# EiBotBoard-v24.net
KiCad netlist of a schematic drawn in EAGLE
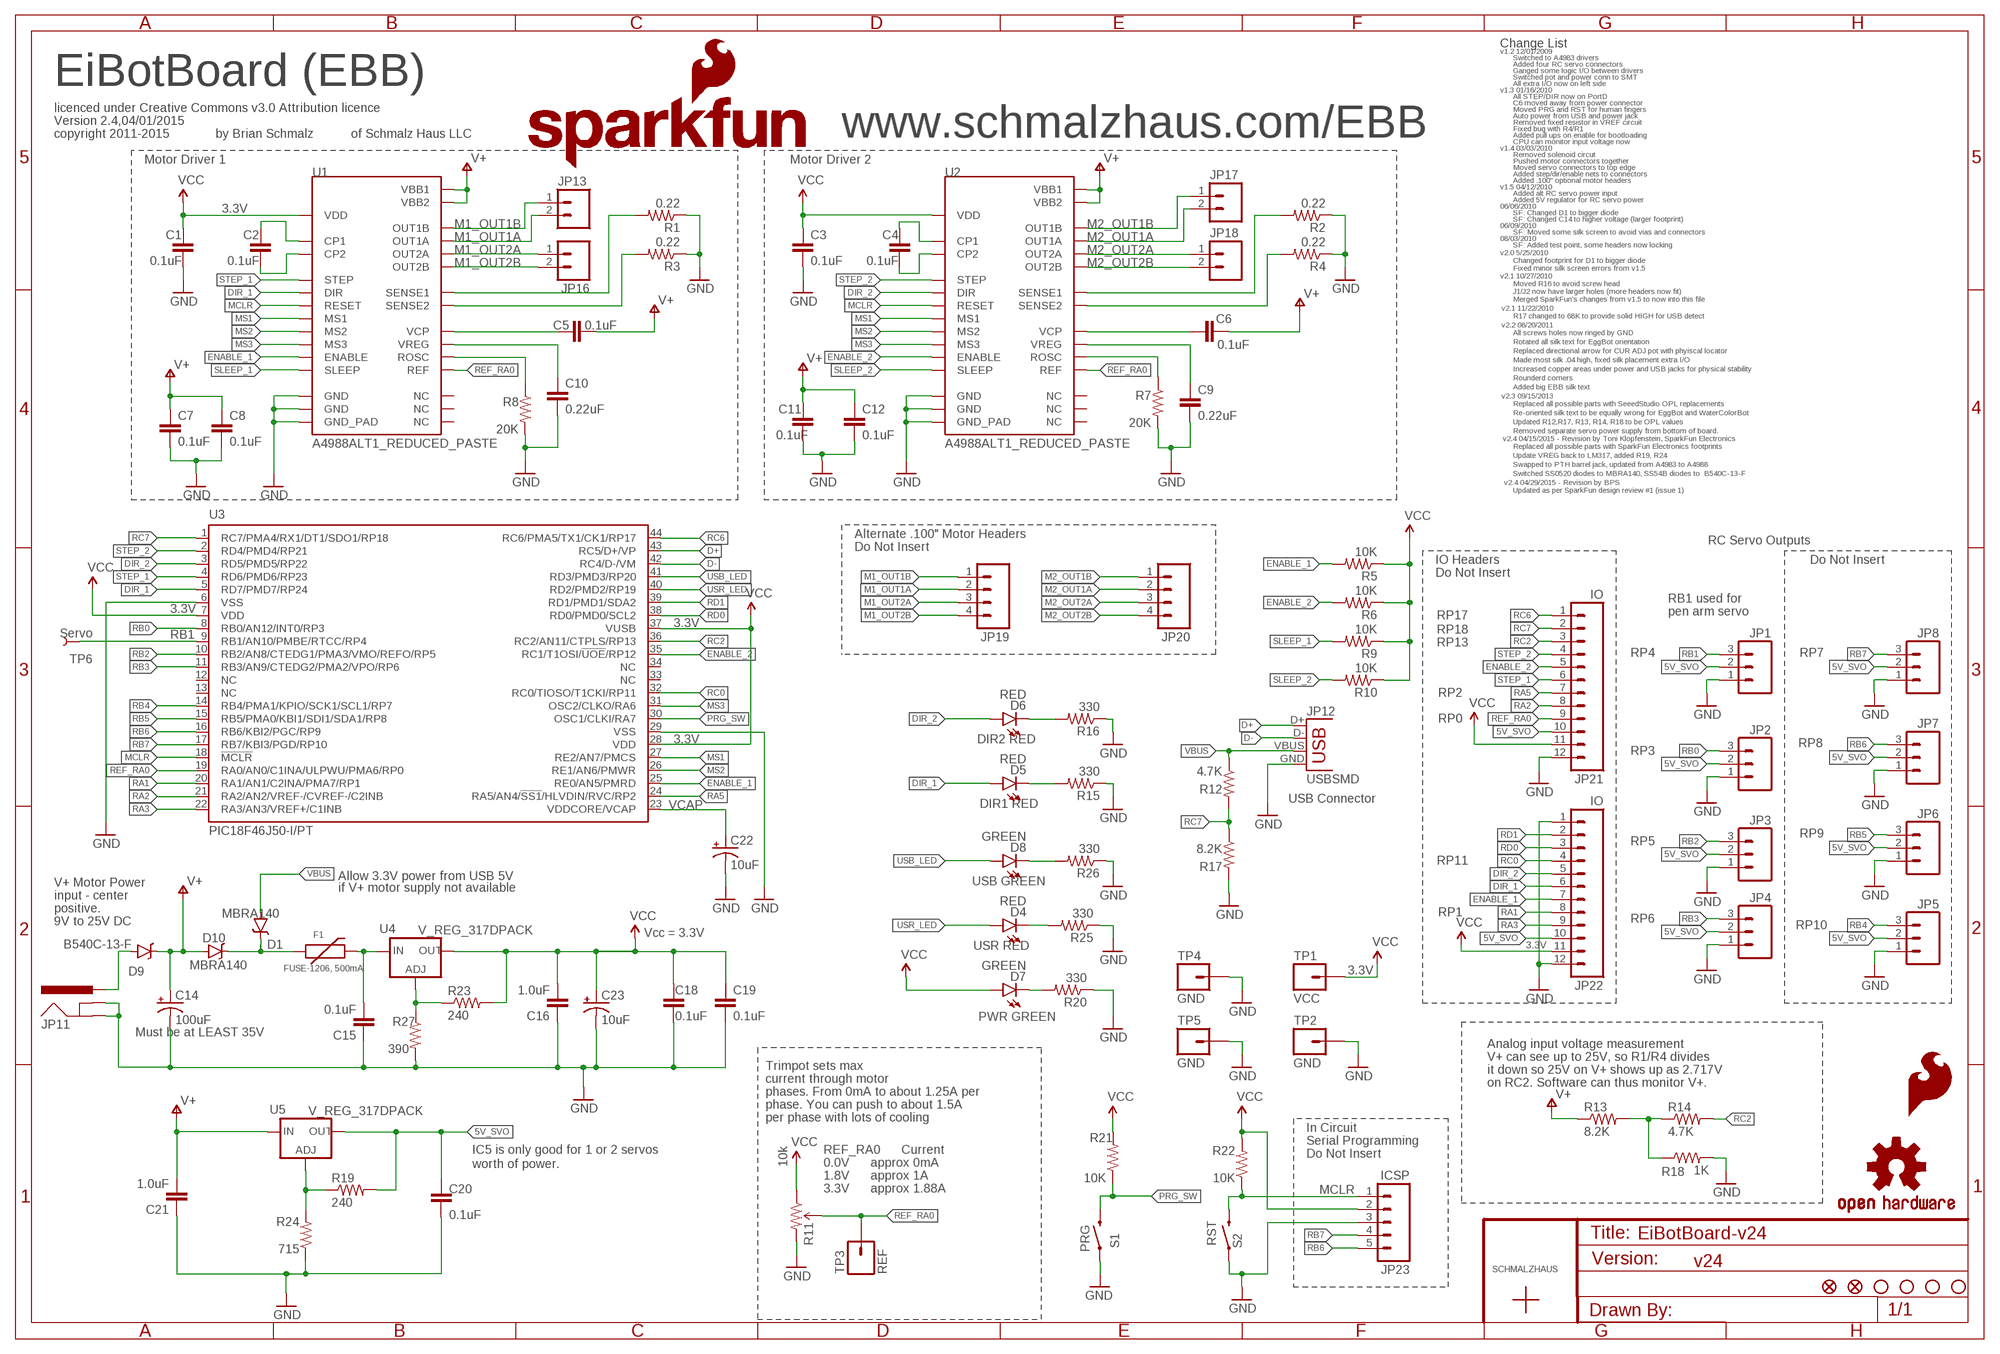
[diagram p0: schematic, sheet 1]

(export (version "E")
  (design (tool "Eeschema 10.0.6"))
  (components
    (comp (ref "C1")
      (value "0.1uF")
      (footprint "eagle-import:0603-CAP")
      (libsource (lib "eagle-import") (part "0.1UF-100V-10%(0603)"))
    )
    (comp (ref "C2")
      (value "0.1uF")
      (footprint "eagle-import:0603-CAP")
      (libsource (lib "eagle-import") (part "0.1UF-100V-10%(0603)"))
    )
    (comp (ref "C3")
      (value "0.1uF")
      (footprint "eagle-import:0603-CAP")
      (libsource (lib "eagle-import") (part "0.1UF-100V-10%(0603)"))
    )
    (comp (ref "C4")
      (value "0.1uF")
      (footprint "eagle-import:0603-CAP")
      (libsource (lib "eagle-import") (part "0.1UF-100V-10%(0603)"))
    )
    (comp (ref "C5")
      (value "0.1uF")
      (footprint "eagle-import:0603-CAP")
      (libsource (lib "eagle-import") (part "0.1UF-100V-10%(0603)"))
    )
    (comp (ref "C6")
      (value "0.1uF")
      (footprint "eagle-import:0603-CAP")
      (libsource (lib "eagle-import") (part "0.1UF-100V-10%(0603)"))
    )
    (comp (ref "C7")
      (value "0.1uF")
      (footprint "eagle-import:0603-CAP")
      (libsource (lib "eagle-import") (part "0.1UF-100V-10%(0603)"))
    )
    (comp (ref "C8")
      (value "0.1uF")
      (footprint "eagle-import:0603-CAP")
      (libsource (lib "eagle-import") (part "0.1UF-100V-10%(0603)"))
    )
    (comp (ref "C9")
      (value "0.22uF")
      (footprint "eagle-import:0603-CAP")
      (libsource (lib "eagle-import") (part "0.22UF50V-20%,+80%(0603)"))
    )
    (comp (ref "C10")
      (value "0.22uF")
      (footprint "eagle-import:0603-CAP")
      (libsource (lib "eagle-import") (part "0.22UF50V-20%,+80%(0603)"))
    )
    (comp (ref "C11")
      (value "0.1uF")
      (footprint "eagle-import:0603-CAP")
      (libsource (lib "eagle-import") (part "0.1UF-100V-10%(0603)"))
    )
    (comp (ref "C12")
      (value "0.1uF")
      (footprint "eagle-import:0603-CAP")
      (libsource (lib "eagle-import") (part "0.1UF-100V-10%(0603)"))
    )
    (comp (ref "C14")
      (value "100uF")
      (footprint "eagle-import:NIC_10X10.5_CAP")
      (libsource (lib "eagle-import") (part "100UF-63V-20%(ELECT)"))
    )
    (comp (ref "C15")
      (value "0.1uF")
      (footprint "eagle-import:0603-CAP")
      (libsource (lib "eagle-import") (part "0.1UF-100V-10%(0603)"))
    )
    (comp (ref "C16")
      (value "1.0uF")
      (footprint "eagle-import:0603-CAP")
      (libsource (lib "eagle-import") (part "1.0UF-16V-10%(0603)"))
    )
    (comp (ref "C18")
      (value "0.1uF")
      (footprint "eagle-import:0603-CAP")
      (libsource (lib "eagle-import") (part "0.1UF-100V-10%(0603)"))
    )
    (comp (ref "C19")
      (value "0.1uF")
      (footprint "eagle-import:0603-CAP")
      (libsource (lib "eagle-import") (part "0.1UF-100V-10%(0603)"))
    )
    (comp (ref "C20")
      (value "0.1uF")
      (footprint "eagle-import:0603-CAP")
      (libsource (lib "eagle-import") (part "0.1UF-100V-10%(0603)"))
    )
    (comp (ref "C21")
      (value "1.0uF")
      (footprint "eagle-import:0603-CAP")
      (libsource (lib "eagle-import") (part "1.0UF-16V-10%(0603)"))
    )
    (comp (ref "C22")
      (value "10uF")
      (footprint "eagle-import:EIA3528")
      (libsource (lib "eagle-import") (part "10UF-20V-10%(TANT)"))
    )
    (comp (ref "C23")
      (value "10uF")
      (footprint "eagle-import:EIA3528")
      (libsource (lib "eagle-import") (part "10UF-20V-10%(TANT)"))
    )
    (comp (ref "D1")
      (value "MBRA140")
      (footprint "eagle-import:SMA-DIODE")
      (libsource (lib "eagle-import") (part "DIODE-SCHOTTKY-MBRA140"))
    )
    (comp (ref "D4")
      (value "RED")
      (footprint "eagle-import:LED-0603")
      (libsource (lib "eagle-import") (part "LED-RED0603"))
    )
    (comp (ref "D5")
      (value "RED")
      (footprint "eagle-import:LED-0603")
      (libsource (lib "eagle-import") (part "LED-RED0603"))
    )
    (comp (ref "D6")
      (value "RED")
      (footprint "eagle-import:LED-0603")
      (libsource (lib "eagle-import") (part "LED-RED0603"))
    )
    (comp (ref "D7")
      (value "GREEN")
      (footprint "eagle-import:LED-0603")
      (libsource (lib "eagle-import") (part "LED-GREEN0603"))
    )
    (comp (ref "D8")
      (value "GREEN")
      (footprint "eagle-import:LED-0603")
      (libsource (lib "eagle-import") (part "LED-GREEN0603"))
    )
    (comp (ref "D9")
      (value "B540C-13-F")
      (footprint "eagle-import:SMC")
      (libsource (lib "eagle-import") (part "DIODE-SCHOTTKY-B540C-13-F"))
    )
    (comp (ref "D10")
      (value "MBRA140")
      (footprint "eagle-import:SMA-DIODE")
      (libsource (lib "eagle-import") (part "DIODE-SCHOTTKY-MBRA140"))
    )
    (comp (ref "F1")
      (value "FUSE-1206, 500mA")
      (footprint "eagle-import:PTC-1206")
      (libsource (lib "eagle-import") (part "PTCTHERMISTOR1206"))
    )
    (comp (ref "JP1")
      (value "M03LOCK_NO_SILK")
      (footprint "eagle-import:1X03_LOCK_NO_SILK")
      (libsource (lib "eagle-import") (part "M03LOCK_NO_SILK"))
    )
    (comp (ref "JP2")
      (value "M03LOCK_NO_SILK")
      (footprint "eagle-import:1X03_LOCK_NO_SILK")
      (libsource (lib "eagle-import") (part "M03LOCK_NO_SILK"))
    )
    (comp (ref "JP3")
      (value "M03LOCK_NO_SILK")
      (footprint "eagle-import:1X03_LOCK_NO_SILK")
      (libsource (lib "eagle-import") (part "M03LOCK_NO_SILK"))
    )
    (comp (ref "JP4")
      (value "M03LOCK_NO_SILK")
      (footprint "eagle-import:1X03_LOCK_NO_SILK")
      (libsource (lib "eagle-import") (part "M03LOCK_NO_SILK"))
    )
    (comp (ref "JP5")
      (value "M03LOCK_NO_SILK")
      (footprint "eagle-import:1X03_LOCK_NO_SILK")
      (libsource (lib "eagle-import") (part "M03LOCK_NO_SILK"))
    )
    (comp (ref "JP6")
      (value "M03LOCK_NO_SILK")
      (footprint "eagle-import:1X03_LOCK_NO_SILK")
      (libsource (lib "eagle-import") (part "M03LOCK_NO_SILK"))
    )
    (comp (ref "JP7")
      (value "M03LOCK_NO_SILK")
      (footprint "eagle-import:1X03_LOCK_NO_SILK")
      (libsource (lib "eagle-import") (part "M03LOCK_NO_SILK"))
    )
    (comp (ref "JP8")
      (value "M03LOCK_NO_SILK")
      (footprint "eagle-import:1X03_LOCK_NO_SILK")
      (libsource (lib "eagle-import") (part "M03LOCK_NO_SILK"))
    )
    (comp (ref "JP11")
      (value "POWER_JACKPTH_LOCK")
      (footprint "eagle-import:POWER_JACK_PTH_LOCK")
      (libsource (lib "eagle-import") (part "POWER_JACKPTH_LOCK"))
    )
    (comp (ref "JP12")
      (value "USBSMD")
      (footprint "eagle-import:USB-MINIB")
      (libsource (lib "eagle-import") (part "USBSMD"))
    )
    (comp (ref "JP13")
      (value "M023.5MM_LOCK")
      (footprint "eagle-import:SCREWTERMINAL-3.5MM-2_LOCK")
      (libsource (lib "eagle-import") (part "M023.5MM_LOCK"))
    )
    (comp (ref "JP14")
      (value "FIDUCIAL1X2")
      (footprint "eagle-import:FIDUCIAL-1X2")
      (libsource (lib "eagle-import") (part "FIDUCIAL1X2"))
    )
    (comp (ref "JP15")
      (value "FIDUCIAL1X2")
      (footprint "eagle-import:FIDUCIAL-1X2")
      (libsource (lib "eagle-import") (part "FIDUCIAL1X2"))
    )
    (comp (ref "JP16")
      (value "M023.5MM_LOCK")
      (footprint "eagle-import:SCREWTERMINAL-3.5MM-2_LOCK")
      (libsource (lib "eagle-import") (part "M023.5MM_LOCK"))
    )
    (comp (ref "JP17")
      (value "M023.5MM_LOCK")
      (footprint "eagle-import:SCREWTERMINAL-3.5MM-2_LOCK")
      (libsource (lib "eagle-import") (part "M023.5MM_LOCK"))
    )
    (comp (ref "JP18")
      (value "M023.5MM_LOCK")
      (footprint "eagle-import:SCREWTERMINAL-3.5MM-2_LOCK")
      (libsource (lib "eagle-import") (part "M023.5MM_LOCK"))
    )
    (comp (ref "JP19")
      (value "M04POLAR")
      (footprint "eagle-import:MOLEX-1X4")
      (libsource (lib "eagle-import") (part "M04POLAR"))
    )
    (comp (ref "JP20")
      (value "M04POLAR")
      (footprint "eagle-import:MOLEX-1X4")
      (libsource (lib "eagle-import") (part "M04POLAR"))
    )
    (comp (ref "JP21")
      (value "IO")
      (footprint "eagle-import:1X12")
      (libsource (lib "eagle-import") (part "M12PTH"))
    )
    (comp (ref "JP22")
      (value "IO")
      (footprint "eagle-import:1X12")
      (libsource (lib "eagle-import") (part "M12PTH"))
    )
    (comp (ref "JP23")
      (value "ICSP")
      (footprint "eagle-import:1X05_NO_SILK")
      (libsource (lib "eagle-import") (part "M05NO_SILK"))
    )
    (comp (ref "LOGO1")
      (value "OSHW-LOGOS")
      (footprint "eagle-import:OSHW-LOGO-S")
      (libsource (lib "eagle-import") (part "OSHW-LOGOS"))
    )
    (comp (ref "LOGO2")
      (value "SFE_LOGO_FLAME.2_INCH")
      (footprint "eagle-import:SFE_LOGO_FLAME_.2")
      (libsource (lib "eagle-import") (part "SFE_LOGO_FLAME.2_INCH"))
    )
    (comp (ref "LOGO3")
      (value "SFE_LOGO_NAME_FLAME.2_INCH")
      (footprint "eagle-import:SFE_LOGO_NAME_FLAME_.2")
      (libsource (lib "eagle-import") (part "SFE_LOGO_NAME_FLAME.2_INCH"))
    )
    (comp (ref "R1")
      (value "0.22")
      (footprint "eagle-import:0805")
      (libsource (lib "eagle-import") (part "0.22OHM-1/4W-1%(0805)"))
    )
    (comp (ref "R2")
      (value "0.22")
      (footprint "eagle-import:0805")
      (libsource (lib "eagle-import") (part "0.22OHM-1/4W-1%(0805)"))
    )
    (comp (ref "R3")
      (value "0.22")
      (footprint "eagle-import:0805")
      (libsource (lib "eagle-import") (part "0.22OHM-1/4W-1%(0805)"))
    )
    (comp (ref "R4")
      (value "0.22")
      (footprint "eagle-import:0805")
      (libsource (lib "eagle-import") (part "0.22OHM-1/4W-1%(0805)"))
    )
    (comp (ref "R5")
      (value "10K")
      (footprint "eagle-import:0603-RES")
      (libsource (lib "eagle-import") (part "10KOHM-1/10W-1%(0603)0603"))
    )
    (comp (ref "R6")
      (value "10K")
      (footprint "eagle-import:0603-RES")
      (libsource (lib "eagle-import") (part "10KOHM-1/10W-1%(0603)0603"))
    )
    (comp (ref "R7")
      (value "20K")
      (footprint "eagle-import:0603-RES")
      (libsource (lib "eagle-import") (part "20KOHM1/10W5%(0603)"))
    )
    (comp (ref "R8")
      (value "20K")
      (footprint "eagle-import:0603-RES")
      (libsource (lib "eagle-import") (part "20KOHM1/10W5%(0603)"))
    )
    (comp (ref "R9")
      (value "10K")
      (footprint "eagle-import:0603-RES")
      (libsource (lib "eagle-import") (part "10KOHM-1/10W-1%(0603)0603"))
    )
    (comp (ref "R10")
      (value "10K")
      (footprint "eagle-import:0603-RES")
      (libsource (lib "eagle-import") (part "10KOHM-1/10W-1%(0603)0603"))
    )
    (comp (ref "R11")
      (value "10k")
      (footprint "eagle-import:TRIMPOT-3MM")
      (libsource (lib "eagle-import") (part "TRIMPOTRES-09285"))
    )
    (comp (ref "R12")
      (value "4.7K")
      (footprint "eagle-import:0603-RES")
      (libsource (lib "eagle-import") (part "4.7KOHM-1/10W-1%(0603)"))
    )
    (comp (ref "R13")
      (value "8.2K")
      (footprint "eagle-import:0603-RES")
      (libsource (lib "eagle-import") (part "8.2KOHM-1/10W-5%(0603)"))
    )
    (comp (ref "R14")
      (value "4.7K")
      (footprint "eagle-import:0603-RES")
      (libsource (lib "eagle-import") (part "4.7KOHM-1/10W-1%(0603)"))
    )
    (comp (ref "R15")
      (value "330")
      (footprint "eagle-import:0603-RES")
      (libsource (lib "eagle-import") (part "330OHM1/10W1%(0603)"))
    )
    (comp (ref "R16")
      (value "330")
      (footprint "eagle-import:0603-RES")
      (libsource (lib "eagle-import") (part "330OHM1/10W1%(0603)"))
    )
    (comp (ref "R17")
      (value "8.2K")
      (footprint "eagle-import:0603-RES")
      (libsource (lib "eagle-import") (part "8.2KOHM-1/10W-5%(0603)"))
    )
    (comp (ref "R18")
      (value "1K")
      (footprint "eagle-import:0603-RES")
      (libsource (lib "eagle-import") (part "1KOHM-1/10W-1%(0603)"))
    )
    (comp (ref "R19")
      (value "240")
      (footprint "eagle-import:0603-RES")
      (libsource (lib "eagle-import") (part "240OHM1/10W1%(0603)"))
    )
    (comp (ref "R20")
      (value "330")
      (footprint "eagle-import:0603-RES")
      (libsource (lib "eagle-import") (part "330OHM1/10W1%(0603)"))
    )
    (comp (ref "R21")
      (value "10K")
      (footprint "eagle-import:0603-RES")
      (libsource (lib "eagle-import") (part "10KOHM-1/10W-1%(0603)0603"))
    )
    (comp (ref "R22")
      (value "10K")
      (footprint "eagle-import:0603-RES")
      (libsource (lib "eagle-import") (part "10KOHM-1/10W-1%(0603)0603"))
    )
    (comp (ref "R23")
      (value "240")
      (footprint "eagle-import:0603-RES")
      (libsource (lib "eagle-import") (part "240OHM1/10W1%(0603)"))
    )
    (comp (ref "R24")
      (value "715")
      (footprint "eagle-import:0603-RES")
      (libsource (lib "eagle-import") (part "715OHM1/10W1%(0603)"))
    )
    (comp (ref "R25")
      (value "330")
      (footprint "eagle-import:0603-RES")
      (libsource (lib "eagle-import") (part "330OHM1/10W1%(0603)"))
    )
    (comp (ref "R26")
      (value "330")
      (footprint "eagle-import:0603-RES")
      (libsource (lib "eagle-import") (part "330OHM1/10W1%(0603)"))
    )
    (comp (ref "R27")
      (value "390")
      (footprint "eagle-import:0603-RES")
      (libsource (lib "eagle-import") (part "390OHM1/10W1%(0603)"))
    )
    (comp (ref "S1")
      (value "SWITCH-MOMENTARY-2SMD")
      (footprint "eagle-import:TACTILE-SWITCH-SMD")
      (libsource (lib "eagle-import") (part "SWITCH-MOMENTARY-2SMD"))
    )
    (comp (ref "S2")
      (value "SWITCH-MOMENTARY-2SMD")
      (footprint "eagle-import:TACTILE-SWITCH-SMD")
      (libsource (lib "eagle-import") (part "SWITCH-MOMENTARY-2SMD"))
    )
    (comp (ref "TP1")
      (value "VCC")
      (footprint "eagle-import:1X01_NOSILK")
      (libsource (lib "eagle-import") (part "M01_WIDENOSLIK"))
    )
    (comp (ref "TP2")
      (value "GND")
      (footprint "eagle-import:1X01_NOSILK")
      (libsource (lib "eagle-import") (part "M01_WIDENOSLIK"))
    )
    (comp (ref "TP3")
      (value "REF")
      (footprint "eagle-import:1X01")
      (libsource (lib "eagle-import") (part "M01PTH"))
    )
    (comp (ref "TP4")
      (value "GND")
      (footprint "eagle-import:1X01_NOSILK")
      (libsource (lib "eagle-import") (part "M01_WIDENOSLIK"))
    )
    (comp (ref "TP5")
      (value "GND")
      (footprint "eagle-import:1X01_NOSILK")
      (libsource (lib "eagle-import") (part "M01_WIDENOSLIK"))
    )
    (comp (ref "TP6")
      (value "Servo")
      (footprint "eagle-import:PAD.03X.05")
      (libsource (lib "eagle-import") (part "TEST-POINT3X5"))
    )
    (comp (ref "U$1")
      (value "SCHMALZHAUSSCHMALZHAUS_SMALL")
      (footprint "eagle-import:SCHMALZHAUS_SMALL")
      (libsource (lib "eagle-import") (part "SCHMALZHAUSSCHMALZHAUS_SMALL"))
    )
    (comp (ref "U$2")
      (value "STAND-OFF")
      (footprint "eagle-import:STAND-OFF")
      (libsource (lib "eagle-import") (part "STAND-OFF"))
    )
    (comp (ref "U$3")
      (value "STAND-OFF")
      (footprint "eagle-import:STAND-OFF")
      (libsource (lib "eagle-import") (part "STAND-OFF"))
    )
    (comp (ref "U$4")
      (value "STAND-OFF")
      (footprint "eagle-import:STAND-OFF")
      (libsource (lib "eagle-import") (part "STAND-OFF"))
    )
    (comp (ref "U$5")
      (value "STAND-OFF")
      (footprint "eagle-import:STAND-OFF")
      (libsource (lib "eagle-import") (part "STAND-OFF"))
    )
    (comp (ref "U1")
      (value "A4988ALT1_REDUCED_PASTE")
      (footprint "eagle-import:QFN-28-5MM_ALT1_REDUCED_PASTE")
      (libsource (lib "eagle-import") (part "A4988ALT1_REDUCED_PASTE"))
    )
    (comp (ref "U2")
      (value "A4988ALT1_REDUCED_PASTE")
      (footprint "eagle-import:QFN-28-5MM_ALT1_REDUCED_PASTE")
      (libsource (lib "eagle-import") (part "A4988ALT1_REDUCED_PASTE"))
    )
    (comp (ref "U3")
      (value "PIC18F46J50-I/PT")
      (footprint "eagle-import:TQFP44")
      (libsource (lib "eagle-import") (part "PIC18F4J50"))
    )
    (comp (ref "U4")
      (value "V_REG_317DPACK")
      (footprint "eagle-import:V-REG_DPACK")
      (libsource (lib "eagle-import") (part "V_REG_317DPACK"))
    )
    (comp (ref "U5")
      (value "V_REG_317DPACK")
      (footprint "eagle-import:V-REG_DPACK")
      (libsource (lib "eagle-import") (part "V_REG_317DPACK"))
    )
  )
  (nets
    (net (code "1") (name "/VCAP") (class "Default")
      (node (ref "C22") (pin "A") (pinfunction "+_A") (pintype "passive"))
      (node (ref "U3") (pin "23") (pinfunction "VDDCORE/VCAP_23") (pintype "bidirectional"))
    )
    (net (code "2") (name "5V_SVO") (class "Default")
      (node (ref "C20") (pin "2") (pinfunction "2_2") (pintype "passive"))
      (node (ref "JP1") (pin "2") (pinfunction "2_2") (pintype "passive"))
      (node (ref "JP2") (pin "2") (pinfunction "2_2") (pintype "passive"))
      (node (ref "JP21") (pin "10") (pinfunction "10_10") (pintype "passive"))
      (node (ref "JP22") (pin "10") (pinfunction "10_10") (pintype "passive"))
      (node (ref "JP3") (pin "2") (pinfunction "2_2") (pintype "passive"))
      (node (ref "JP4") (pin "2") (pinfunction "2_2") (pintype "passive"))
      (node (ref "JP5") (pin "2") (pinfunction "2_2") (pintype "passive"))
      (node (ref "JP6") (pin "2") (pinfunction "2_2") (pintype "passive"))
      (node (ref "JP7") (pin "2") (pinfunction "2_2") (pintype "passive"))
      (node (ref "JP8") (pin "2") (pinfunction "2_2") (pintype "passive"))
      (node (ref "R19") (pin "2") (pinfunction "2_2") (pintype "passive"))
      (node (ref "U5") (pin "4") (pinfunction "OUT_4") (pintype "output"))
    )
    (net (code "3") (name "D+") (class "Default")
      (node (ref "JP12") (pin "D+") (pinfunction "D+_D+") (pintype "bidirectional"))
      (node (ref "U3") (pin "43") (pinfunction "RC5/D+/VP_43") (pintype "bidirectional"))
    )
    (net (code "4") (name "D-") (class "Default")
      (node (ref "JP12") (pin "D-") (pinfunction "D-_D-") (pintype "bidirectional"))
      (node (ref "U3") (pin "42") (pinfunction "RC4/D-/VM_42") (pintype "bidirectional"))
    )
    (net (code "5") (name "DIR_1") (class "Default")
      (node (ref "D5") (pin "A") (pinfunction "A_A") (pintype "passive"))
      (node (ref "JP22") (pin "6") (pinfunction "6_6") (pintype "passive"))
      (node (ref "U1") (pin "P$19") (pinfunction "DIR_P$19") (pintype "input"))
      (node (ref "U3") (pin "5") (pinfunction "RD7/PMD7/RP24_5") (pintype "bidirectional"))
    )
    (net (code "6") (name "DIR_2") (class "Default")
      (node (ref "D6") (pin "A") (pinfunction "A_A") (pintype "passive"))
      (node (ref "JP22") (pin "5") (pinfunction "5_5") (pintype "passive"))
      (node (ref "U2") (pin "P$19") (pinfunction "DIR_P$19") (pintype "input"))
      (node (ref "U3") (pin "3") (pinfunction "RD5/PMD5/RP22_3") (pintype "bidirectional"))
    )
    (net (code "7") (name "ENABLE_1") (class "Default")
      (node (ref "JP22") (pin "7") (pinfunction "7_7") (pintype "passive"))
      (node (ref "R5") (pin "2") (pinfunction "2_2") (pintype "passive"))
      (node (ref "U1") (pin "P$2") (pinfunction "ENABLE_P$2") (pintype "input"))
      (node (ref "U3") (pin "25") (pinfunction "RE0/AN5/PMRD_25") (pintype "bidirectional"))
    )
    (net (code "8") (name "ENABLE_2") (class "Default")
      (node (ref "JP21") (pin "5") (pinfunction "5_5") (pintype "passive"))
      (node (ref "R6") (pin "2") (pinfunction "2_2") (pintype "passive"))
      (node (ref "U2") (pin "P$2") (pinfunction "ENABLE_P$2") (pintype "input"))
      (node (ref "U3") (pin "35") (pinfunction "RC1/T1OSI/~{UOE}/RP12_35") (pintype "bidirectional"))
    )
    (net (code "9") (name "GND") (class "Default")
      (node (ref "C1") (pin "2") (pinfunction "2_2") (pintype "passive"))
      (node (ref "C10") (pin "2") (pinfunction "2_2") (pintype "passive"))
      (node (ref "C11") (pin "2") (pinfunction "2_2") (pintype "passive"))
      (node (ref "C12") (pin "2") (pinfunction "2_2") (pintype "passive"))
      (node (ref "C14") (pin "-") (pinfunction "-_-") (pintype "passive"))
      (node (ref "C15") (pin "1") (pinfunction "1_1") (pintype "passive"))
      (node (ref "C16") (pin "1") (pinfunction "1_1") (pintype "passive"))
      (node (ref "C18") (pin "1") (pinfunction "1_1") (pintype "passive"))
      (node (ref "C19") (pin "1") (pinfunction "1_1") (pintype "passive"))
      (node (ref "C20") (pin "1") (pinfunction "1_1") (pintype "passive"))
      (node (ref "C21") (pin "1") (pinfunction "1_1") (pintype "passive"))
      (node (ref "C22") (pin "C") (pinfunction "-_C") (pintype "passive"))
      (node (ref "C23") (pin "C") (pinfunction "-_C") (pintype "passive"))
      (node (ref "C3") (pin "2") (pinfunction "2_2") (pintype "passive"))
      (node (ref "C7") (pin "2") (pinfunction "2_2") (pintype "passive"))
      (node (ref "C8") (pin "2") (pinfunction "2_2") (pintype "passive"))
      (node (ref "C9") (pin "2") (pinfunction "2_2") (pintype "passive"))
      (node (ref "JP1") (pin "1") (pinfunction "1_1") (pintype "passive"))
      (node (ref "JP11") (pin "GND") (pinfunction "GND_GND") (pintype "bidirectional"))
      (node (ref "JP11") (pin "GNDBREAK") (pinfunction "GNDBREAK_GNDBREAK") (pintype "bidirectional"))
      (node (ref "JP12") (pin "GND") (pinfunction "GND_GND") (pintype "bidirectional"))
      (node (ref "JP2") (pin "1") (pinfunction "1_1") (pintype "passive"))
      (node (ref "JP21") (pin "12") (pinfunction "12_12") (pintype "passive"))
      (node (ref "JP22") (pin "1") (pinfunction "1_1") (pintype "passive"))
      (node (ref "JP22") (pin "12") (pinfunction "12_12") (pintype "passive"))
      (node (ref "JP23") (pin "3") (pinfunction "3_3") (pintype "passive"))
      (node (ref "JP3") (pin "1") (pinfunction "1_1") (pintype "passive"))
      (node (ref "JP4") (pin "1") (pinfunction "1_1") (pintype "passive"))
      (node (ref "JP5") (pin "1") (pinfunction "1_1") (pintype "passive"))
      (node (ref "JP6") (pin "1") (pinfunction "1_1") (pintype "passive"))
      (node (ref "JP7") (pin "1") (pinfunction "1_1") (pintype "passive"))
      (node (ref "JP8") (pin "1") (pinfunction "1_1") (pintype "passive"))
      (node (ref "R1") (pin "1") (pinfunction "1_1") (pintype "passive"))
      (node (ref "R11") (pin "3") (pinfunction "CW_3") (pintype "passive"))
      (node (ref "R15") (pin "1") (pinfunction "1_1") (pintype "passive"))
      (node (ref "R16") (pin "1") (pinfunction "1_1") (pintype "passive"))
      (node (ref "R17") (pin "2") (pinfunction "2_2") (pintype "passive"))
      (node (ref "R18") (pin "2") (pinfunction "2_2") (pintype "passive"))
      (node (ref "R2") (pin "1") (pinfunction "1_1") (pintype "passive"))
      (node (ref "R20") (pin "1") (pinfunction "1_1") (pintype "passive"))
      (node (ref "R24") (pin "1") (pinfunction "1_1") (pintype "passive"))
      (node (ref "R25") (pin "1") (pinfunction "1_1") (pintype "passive"))
      (node (ref "R26") (pin "1") (pinfunction "1_1") (pintype "passive"))
      (node (ref "R27") (pin "2") (pinfunction "2_2") (pintype "passive"))
      (node (ref "R3") (pin "1") (pinfunction "1_1") (pintype "passive"))
      (node (ref "R4") (pin "1") (pinfunction "1_1") (pintype "passive"))
      (node (ref "R7") (pin "2") (pinfunction "2_2") (pintype "passive"))
      (node (ref "R8") (pin "2") (pinfunction "2_2") (pintype "passive"))
      (node (ref "S1") (pin "1") (pinfunction "1_1") (pintype "passive"))
      (node (ref "S2") (pin "1") (pinfunction "1_1") (pintype "passive"))
      (node (ref "TP2") (pin "1") (pinfunction "1_1") (pintype "passive"))
      (node (ref "TP4") (pin "1") (pinfunction "1_1") (pintype "passive"))
      (node (ref "TP5") (pin "1") (pinfunction "1_1") (pintype "passive"))
      (node (ref "U1") (pin "P$18") (pinfunction "GND_P$18") (pintype "power_in"))
      (node (ref "U1") (pin "P$29") (pinfunction "GND_PAD_P$29") (pintype "power_in"))
      (node (ref "U1") (pin "P$3") (pinfunction "GND_P$3") (pintype "power_in"))
      (node (ref "U2") (pin "P$18") (pinfunction "GND_P$18") (pintype "power_in"))
      (node (ref "U2") (pin "P$29") (pinfunction "GND_PAD_P$29") (pintype "power_in"))
      (node (ref "U2") (pin "P$3") (pinfunction "GND_P$3") (pintype "power_in"))
      (node (ref "U3") (pin "29") (pinfunction "VSS_29") (pintype "power_in"))
      (node (ref "U3") (pin "6") (pinfunction "VSS_6") (pintype "power_in"))
    )
    (net (code "10") (name "M1_OUT1A") (class "Default")
      (node (ref "JP13") (pin "2") (pinfunction "2_2") (pintype "passive"))
      (node (ref "JP19") (pin "2") (pinfunction "2_2") (pintype "passive"))
      (node (ref "U1") (pin "P$24") (pinfunction "OUT1A_P$24") (pintype "bidirectional"))
    )
    (net (code "11") (name "M1_OUT1B") (class "Default")
      (node (ref "JP13") (pin "1") (pinfunction "1_1") (pintype "passive"))
      (node (ref "JP19") (pin "1") (pinfunction "1_1") (pintype "passive"))
      (node (ref "U1") (pin "P$21") (pinfunction "OUT1B_P$21") (pintype "bidirectional"))
    )
    (net (code "12") (name "M1_OUT2A") (class "Default")
      (node (ref "JP16") (pin "1") (pinfunction "1_1") (pintype "passive"))
      (node (ref "JP19") (pin "3") (pinfunction "3_3") (pintype "passive"))
      (node (ref "U1") (pin "P$26") (pinfunction "OUT2A_P$26") (pintype "bidirectional"))
    )
    (net (code "13") (name "M1_OUT2B") (class "Default")
      (node (ref "JP16") (pin "2") (pinfunction "2_2") (pintype "passive"))
      (node (ref "JP19") (pin "4") (pinfunction "4_4") (pintype "passive"))
      (node (ref "U1") (pin "P$1") (pinfunction "OUT2B_P$1") (pintype "bidirectional"))
    )
    (net (code "14") (name "M2_OUT1A") (class "Default")
      (node (ref "JP17") (pin "2") (pinfunction "2_2") (pintype "passive"))
      (node (ref "JP20") (pin "2") (pinfunction "2_2") (pintype "passive"))
      (node (ref "U2") (pin "P$24") (pinfunction "OUT1A_P$24") (pintype "bidirectional"))
    )
    (net (code "15") (name "M2_OUT1B") (class "Default")
      (node (ref "JP17") (pin "1") (pinfunction "1_1") (pintype "passive"))
      (node (ref "JP20") (pin "1") (pinfunction "1_1") (pintype "passive"))
      (node (ref "U2") (pin "P$21") (pinfunction "OUT1B_P$21") (pintype "bidirectional"))
    )
    (net (code "16") (name "M2_OUT2A") (class "Default")
      (node (ref "JP18") (pin "1") (pinfunction "1_1") (pintype "passive"))
      (node (ref "JP20") (pin "3") (pinfunction "3_3") (pintype "passive"))
      (node (ref "U2") (pin "P$26") (pinfunction "OUT2A_P$26") (pintype "bidirectional"))
    )
    (net (code "17") (name "M2_OUT2B") (class "Default")
      (node (ref "JP18") (pin "2") (pinfunction "2_2") (pintype "passive"))
      (node (ref "JP20") (pin "4") (pinfunction "4_4") (pintype "passive"))
      (node (ref "U2") (pin "P$1") (pinfunction "OUT2B_P$1") (pintype "bidirectional"))
    )
    (net (code "18") (name "MCLR") (class "Default")
      (node (ref "JP23") (pin "1") (pinfunction "1_1") (pintype "passive"))
      (node (ref "R22") (pin "1") (pinfunction "1_1") (pintype "passive"))
      (node (ref "S2") (pin "3") (pinfunction "2_3") (pintype "passive"))
      (node (ref "U1") (pin "P$12") (pinfunction "RESET_P$12") (pintype "input"))
      (node (ref "U2") (pin "P$12") (pinfunction "RESET_P$12") (pintype "input"))
      (node (ref "U3") (pin "18") (pinfunction "~{MCLR}_18") (pintype "input"))
    )
    (net (code "19") (name "MS1") (class "Default")
      (node (ref "U1") (pin "P$9") (pinfunction "MS1_P$9") (pintype "input"))
      (node (ref "U2") (pin "P$9") (pinfunction "MS1_P$9") (pintype "input"))
      (node (ref "U3") (pin "27") (pinfunction "RE2/AN7/PMCS_27") (pintype "bidirectional"))
    )
    (net (code "20") (name "MS2") (class "Default")
      (node (ref "U1") (pin "P$10") (pinfunction "MS2_P$10") (pintype "input"))
      (node (ref "U2") (pin "P$10") (pinfunction "MS2_P$10") (pintype "input"))
      (node (ref "U3") (pin "26") (pinfunction "RE1/AN6/PMWR_26") (pintype "bidirectional"))
    )
    (net (code "21") (name "MS3") (class "Default")
      (node (ref "U1") (pin "P$11") (pinfunction "MS3_P$11") (pintype "input"))
      (node (ref "U2") (pin "P$11") (pinfunction "MS3_P$11") (pintype "input"))
      (node (ref "U3") (pin "31") (pinfunction "OSC2/CLKO/RA6_31") (pintype "output"))
    )
    (net (code "22") (name "Net-(D1-PadC)") (class "Default")
      (node (ref "D1") (pin "C") (pinfunction "C_C") (pintype "passive"))
      (node (ref "D10") (pin "C") (pinfunction "C_C") (pintype "passive"))
      (node (ref "F1") (pin "1") (pinfunction "1_1") (pintype "bidirectional"))
    )
    (net (code "23") (name "Net-(D4-PadC)") (class "Default")
      (node (ref "D4") (pin "C") (pinfunction "C_C") (pintype "passive"))
      (node (ref "R25") (pin "2") (pinfunction "2_2") (pintype "passive"))
    )
    (net (code "24") (name "Net-(D5-PadC)") (class "Default")
      (node (ref "D5") (pin "C") (pinfunction "C_C") (pintype "passive"))
      (node (ref "R15") (pin "2") (pinfunction "2_2") (pintype "passive"))
    )
    (net (code "25") (name "Net-(D6-PadC)") (class "Default")
      (node (ref "D6") (pin "C") (pinfunction "C_C") (pintype "passive"))
      (node (ref "R16") (pin "2") (pinfunction "2_2") (pintype "passive"))
    )
    (net (code "26") (name "Net-(D7-PadC)") (class "Default")
      (node (ref "D7") (pin "C") (pinfunction "C_C") (pintype "passive"))
      (node (ref "R20") (pin "2") (pinfunction "2_2") (pintype "passive"))
    )
    (net (code "27") (name "Net-(D8-PadC)") (class "Default")
      (node (ref "D8") (pin "C") (pinfunction "C_C") (pintype "passive"))
      (node (ref "R26") (pin "2") (pinfunction "2_2") (pintype "passive"))
    )
    (net (code "28") (name "Net-(D9-PadA)") (class "Default")
      (node (ref "D9") (pin "A") (pinfunction "A_A") (pintype "passive"))
      (node (ref "JP11") (pin "PWR") (pinfunction "PWR_PWR") (pintype "bidirectional"))
    )
    (net (code "29") (name "Net-(R13-Pad2)") (class "Default")
      (node (ref "R13") (pin "2") (pinfunction "2_2") (pintype "passive"))
      (node (ref "R14") (pin "1") (pinfunction "1_1") (pintype "passive"))
      (node (ref "R18") (pin "1") (pinfunction "1_1") (pintype "passive"))
    )
    (net (code "30") (name "Net-(U1-CP1)") (class "Default")
      (node (ref "C2") (pin "1") (pinfunction "1_1") (pintype "passive"))
      (node (ref "U1") (pin "P$4") (pinfunction "CP1_P$4") (pintype "bidirectional"))
    )
    (net (code "31") (name "Net-(U1-CP2)") (class "Default")
      (node (ref "C2") (pin "2") (pinfunction "2_2") (pintype "passive"))
      (node (ref "U1") (pin "P$5") (pinfunction "CP2_P$5") (pintype "bidirectional"))
    )
    (net (code "32") (name "Net-(U1-ROSC)") (class "Default")
      (node (ref "R8") (pin "1") (pinfunction "1_1") (pintype "passive"))
      (node (ref "U1") (pin "P$13") (pinfunction "ROSC_P$13") (pintype "bidirectional"))
    )
    (net (code "33") (name "Net-(U1-SENSE1)") (class "Default")
      (node (ref "R1") (pin "2") (pinfunction "2_2") (pintype "passive"))
      (node (ref "U1") (pin "P$23") (pinfunction "SENSE1_P$23") (pintype "bidirectional"))
    )
    (net (code "34") (name "Net-(U1-SENSE2)") (class "Default")
      (node (ref "R3") (pin "2") (pinfunction "2_2") (pintype "passive"))
      (node (ref "U1") (pin "P$27") (pinfunction "SENSE2_P$27") (pintype "bidirectional"))
    )
    (net (code "35") (name "Net-(U1-VCP)") (class "Default")
      (node (ref "C5") (pin "1") (pinfunction "1_1") (pintype "passive"))
      (node (ref "U1") (pin "P$6") (pinfunction "VCP_P$6") (pintype "bidirectional"))
    )
    (net (code "36") (name "Net-(U1-VREG)") (class "Default")
      (node (ref "C10") (pin "1") (pinfunction "1_1") (pintype "passive"))
      (node (ref "U1") (pin "P$8") (pinfunction "VREG_P$8") (pintype "bidirectional"))
    )
    (net (code "37") (name "Net-(U2-CP1)") (class "Default")
      (node (ref "C4") (pin "1") (pinfunction "1_1") (pintype "passive"))
      (node (ref "U2") (pin "P$4") (pinfunction "CP1_P$4") (pintype "bidirectional"))
    )
    (net (code "38") (name "Net-(U2-CP2)") (class "Default")
      (node (ref "C4") (pin "2") (pinfunction "2_2") (pintype "passive"))
      (node (ref "U2") (pin "P$5") (pinfunction "CP2_P$5") (pintype "bidirectional"))
    )
    (net (code "39") (name "Net-(U2-ROSC)") (class "Default")
      (node (ref "R7") (pin "1") (pinfunction "1_1") (pintype "passive"))
      (node (ref "U2") (pin "P$13") (pinfunction "ROSC_P$13") (pintype "bidirectional"))
    )
    (net (code "40") (name "Net-(U2-SENSE1)") (class "Default")
      (node (ref "R2") (pin "2") (pinfunction "2_2") (pintype "passive"))
      (node (ref "U2") (pin "P$23") (pinfunction "SENSE1_P$23") (pintype "bidirectional"))
    )
    (net (code "41") (name "Net-(U2-SENSE2)") (class "Default")
      (node (ref "R4") (pin "2") (pinfunction "2_2") (pintype "passive"))
      (node (ref "U2") (pin "P$27") (pinfunction "SENSE2_P$27") (pintype "bidirectional"))
    )
    (net (code "42") (name "Net-(U2-VCP)") (class "Default")
      (node (ref "C6") (pin "1") (pinfunction "1_1") (pintype "passive"))
      (node (ref "U2") (pin "P$6") (pinfunction "VCP_P$6") (pintype "bidirectional"))
    )
    (net (code "43") (name "Net-(U2-VREG)") (class "Default")
      (node (ref "C9") (pin "1") (pinfunction "1_1") (pintype "passive"))
      (node (ref "U2") (pin "P$8") (pinfunction "VREG_P$8") (pintype "bidirectional"))
    )
    (net (code "44") (name "Net-(U4-ADJ)") (class "Default")
      (node (ref "R23") (pin "1") (pinfunction "1_1") (pintype "passive"))
      (node (ref "R27") (pin "1") (pinfunction "1_1") (pintype "passive"))
      (node (ref "U4") (pin "1") (pinfunction "ADJ_1") (pintype "input"))
    )
    (net (code "45") (name "Net-(U4-IN)") (class "Default")
      (node (ref "C15") (pin "2") (pinfunction "2_2") (pintype "passive"))
      (node (ref "F1") (pin "2") (pinfunction "2_2") (pintype "bidirectional"))
      (node (ref "U4") (pin "3") (pinfunction "IN_3") (pintype "input"))
    )
    (net (code "46") (name "Net-(U5-ADJ)") (class "Default")
      (node (ref "R19") (pin "1") (pinfunction "1_1") (pintype "passive"))
      (node (ref "R24") (pin "2") (pinfunction "2_2") (pintype "passive"))
      (node (ref "U5") (pin "1") (pinfunction "ADJ_1") (pintype "input"))
    )
    (net (code "47") (name "PRG_SW") (class "Default")
      (node (ref "R21") (pin "1") (pinfunction "1_1") (pintype "passive"))
      (node (ref "S1") (pin "3") (pinfunction "2_3") (pintype "passive"))
      (node (ref "U3") (pin "30") (pinfunction "OSC1/CLKI/RA7_30") (pintype "input"))
    )
    (net (code "48") (name "RA1") (class "Default")
      (node (ref "JP22") (pin "8") (pinfunction "8_8") (pintype "passive"))
      (node (ref "U3") (pin "20") (pinfunction "RA1/AN1/C2INA/PMA7/RP1_20") (pintype "bidirectional"))
    )
    (net (code "49") (name "RA2") (class "Default")
      (node (ref "JP21") (pin "8") (pinfunction "8_8") (pintype "passive"))
      (node (ref "U3") (pin "21") (pinfunction "RA2/AN2/VREF-/CVREF-/C2INB_21") (pintype "bidirectional"))
    )
    (net (code "50") (name "RA3") (class "Default")
      (node (ref "JP22") (pin "9") (pinfunction "9_9") (pintype "passive"))
      (node (ref "U3") (pin "22") (pinfunction "RA3/AN3/VREF+/C1INB_22") (pintype "bidirectional"))
    )
    (net (code "51") (name "RA5") (class "Default")
      (node (ref "JP21") (pin "7") (pinfunction "7_7") (pintype "passive"))
      (node (ref "U3") (pin "24") (pinfunction "RA5/AN4/~{SS1}/HLVDIN/RVC/RP2_24") (pintype "bidirectional"))
    )
    (net (code "52") (name "RB0") (class "Default")
      (node (ref "JP2") (pin "3") (pinfunction "3_3") (pintype "passive"))
      (node (ref "U3") (pin "8") (pinfunction "RB0/AN12/INT0/RP3_8") (pintype "bidirectional"))
    )
    (net (code "53") (name "RB1") (class "Default")
      (node (ref "JP1") (pin "3") (pinfunction "3_3") (pintype "passive"))
      (node (ref "TP6") (pin "P$1") (pinfunction "1_P$1") (pintype "bidirectional"))
      (node (ref "U3") (pin "9") (pinfunction "RB1/AN10/PMBE/RTCC/RP4_9") (pintype "bidirectional"))
    )
    (net (code "54") (name "RB2") (class "Default")
      (node (ref "JP3") (pin "3") (pinfunction "3_3") (pintype "passive"))
      (node (ref "U3") (pin "10") (pinfunction "RB2/AN8/CTEDG1/PMA3/VMO/REFO/RP5_10") (pintype "bidirectional"))
    )
    (net (code "55") (name "RB3") (class "Default")
      (node (ref "JP4") (pin "3") (pinfunction "3_3") (pintype "passive"))
      (node (ref "U3") (pin "11") (pinfunction "RB3/AN9/CTEDG2/PMA2/VPO/RP6_11") (pintype "bidirectional"))
    )
    (net (code "56") (name "RB4") (class "Default")
      (node (ref "JP5") (pin "3") (pinfunction "3_3") (pintype "passive"))
      (node (ref "U3") (pin "14") (pinfunction "RB4/PMA1/KPIO/SCK1/SCL1/RP7_14") (pintype "bidirectional"))
    )
    (net (code "57") (name "RB5") (class "Default")
      (node (ref "JP6") (pin "3") (pinfunction "3_3") (pintype "passive"))
      (node (ref "U3") (pin "15") (pinfunction "RB5/PMA0/KBI1/SDI1/SDA1/RP8_15") (pintype "bidirectional"))
    )
    (net (code "58") (name "RB6") (class "Default")
      (node (ref "JP23") (pin "5") (pinfunction "5_5") (pintype "passive"))
      (node (ref "JP7") (pin "3") (pinfunction "3_3") (pintype "passive"))
      (node (ref "U3") (pin "16") (pinfunction "RB6/KBI2/PGC/RP9_16") (pintype "bidirectional"))
    )
    (net (code "59") (name "RB7") (class "Default")
      (node (ref "JP23") (pin "4") (pinfunction "4_4") (pintype "passive"))
      (node (ref "JP8") (pin "3") (pinfunction "3_3") (pintype "passive"))
      (node (ref "U3") (pin "17") (pinfunction "RB7/KBI3/PGD/RP10_17") (pintype "bidirectional"))
    )
    (net (code "60") (name "RC0") (class "Default")
      (node (ref "JP22") (pin "4") (pinfunction "4_4") (pintype "passive"))
      (node (ref "U3") (pin "32") (pinfunction "RC0/TIOSO/T1CKI/RP11_32") (pintype "bidirectional"))
    )
    (net (code "61") (name "RC2") (class "Default")
      (node (ref "JP21") (pin "3") (pinfunction "3_3") (pintype "passive"))
      (node (ref "R14") (pin "2") (pinfunction "2_2") (pintype "passive"))
      (node (ref "U3") (pin "36") (pinfunction "RC2/AN11/CTPLS/RP13_36") (pintype "bidirectional"))
    )
    (net (code "62") (name "RC6") (class "Default")
      (node (ref "JP21") (pin "1") (pinfunction "1_1") (pintype "passive"))
      (node (ref "U3") (pin "44") (pinfunction "RC6/PMA5/TX1/CK1/RP17_44") (pintype "bidirectional"))
    )
    (net (code "63") (name "RC7") (class "Default")
      (node (ref "JP21") (pin "2") (pinfunction "2_2") (pintype "passive"))
      (node (ref "R12") (pin "2") (pinfunction "2_2") (pintype "passive"))
      (node (ref "R17") (pin "1") (pinfunction "1_1") (pintype "passive"))
      (node (ref "U3") (pin "1") (pinfunction "RC7/PMA4/RX1/DT1/SDO1/RP18_1") (pintype "bidirectional"))
    )
    (net (code "64") (name "RD0") (class "Default")
      (node (ref "JP22") (pin "3") (pinfunction "3_3") (pintype "passive"))
      (node (ref "U3") (pin "38") (pinfunction "RD0/PMD0/SCL2_38") (pintype "bidirectional"))
    )
    (net (code "65") (name "RD1") (class "Default")
      (node (ref "JP22") (pin "2") (pinfunction "2_2") (pintype "passive"))
      (node (ref "U3") (pin "39") (pinfunction "RD1/PMD1/SDA2_39") (pintype "bidirectional"))
    )
    (net (code "66") (name "REF_RA0") (class "Default")
      (node (ref "JP21") (pin "9") (pinfunction "9_9") (pintype "passive"))
      (node (ref "R11") (pin "2") (pinfunction "WIPER_2") (pintype "passive"))
      (node (ref "TP3") (pin "1") (pinfunction "1_1") (pintype "passive"))
      (node (ref "U1") (pin "P$17") (pinfunction "REF_P$17") (pintype "bidirectional"))
      (node (ref "U2") (pin "P$17") (pinfunction "REF_P$17") (pintype "bidirectional"))
      (node (ref "U3") (pin "19") (pinfunction "RA0/AN0/C1INA/ULPWU/PMA6/RP0_19") (pintype "bidirectional"))
    )
    (net (code "67") (name "SLEEP_1") (class "Default")
      (node (ref "R9") (pin "2") (pinfunction "2_2") (pintype "passive"))
      (node (ref "U1") (pin "P$14") (pinfunction "SLEEP_P$14") (pintype "input"))
    )
    (net (code "68") (name "SLEEP_2") (class "Default")
      (node (ref "R10") (pin "2") (pinfunction "2_2") (pintype "passive"))
      (node (ref "U2") (pin "P$14") (pinfunction "SLEEP_P$14") (pintype "input"))
    )
    (net (code "69") (name "STEP_1") (class "Default")
      (node (ref "JP21") (pin "6") (pinfunction "6_6") (pintype "passive"))
      (node (ref "U1") (pin "P$16") (pinfunction "STEP_P$16") (pintype "input"))
      (node (ref "U3") (pin "4") (pinfunction "RD6/PMD6/RP23_4") (pintype "bidirectional"))
    )
    (net (code "70") (name "STEP_2") (class "Default")
      (node (ref "JP21") (pin "4") (pinfunction "4_4") (pintype "passive"))
      (node (ref "U2") (pin "P$16") (pinfunction "STEP_P$16") (pintype "input"))
      (node (ref "U3") (pin "2") (pinfunction "RD4/PMD4/RP21_2") (pintype "bidirectional"))
    )
    (net (code "71") (name "USB_LED") (class "Default")
      (node (ref "D8") (pin "A") (pinfunction "A_A") (pintype "passive"))
      (node (ref "U3") (pin "41") (pinfunction "RD3/PMD3/RP20_41") (pintype "bidirectional"))
    )
    (net (code "72") (name "USR_LED") (class "Default")
      (node (ref "D4") (pin "A") (pinfunction "A_A") (pintype "passive"))
      (node (ref "U3") (pin "40") (pinfunction "RD2/PMD2/RP19_40") (pintype "bidirectional"))
    )
    (net (code "73") (name "V+") (class "Default")
      (node (ref "C11") (pin "1") (pinfunction "1_1") (pintype "passive"))
      (node (ref "C12") (pin "1") (pinfunction "1_1") (pintype "passive"))
      (node (ref "C14") (pin "+") (pinfunction "+_+") (pintype "passive"))
      (node (ref "C21") (pin "2") (pinfunction "2_2") (pintype "passive"))
      (node (ref "C5") (pin "2") (pinfunction "2_2") (pintype "passive"))
      (node (ref "C6") (pin "2") (pinfunction "2_2") (pintype "passive"))
      (node (ref "C7") (pin "1") (pinfunction "1_1") (pintype "passive"))
      (node (ref "C8") (pin "1") (pinfunction "1_1") (pintype "passive"))
      (node (ref "D10") (pin "A") (pinfunction "A_A") (pintype "passive"))
      (node (ref "D9") (pin "C") (pinfunction "C_C") (pintype "passive"))
      (node (ref "R13") (pin "1") (pinfunction "1_1") (pintype "passive"))
      (node (ref "U1") (pin "P$22") (pinfunction "VBB1_P$22") (pintype "bidirectional"))
      (node (ref "U1") (pin "P$28") (pinfunction "VBB2_P$28") (pintype "bidirectional"))
      (node (ref "U2") (pin "P$22") (pinfunction "VBB1_P$22") (pintype "bidirectional"))
      (node (ref "U2") (pin "P$28") (pinfunction "VBB2_P$28") (pintype "bidirectional"))
      (node (ref "U5") (pin "3") (pinfunction "IN_3") (pintype "input"))
    )
    (net (code "74") (name "VBUS") (class "Default")
      (node (ref "D1") (pin "A") (pinfunction "A_A") (pintype "passive"))
      (node (ref "JP12") (pin "VBUS") (pinfunction "VBUS_VBUS") (pintype "bidirectional"))
      (node (ref "R12") (pin "1") (pinfunction "1_1") (pintype "passive"))
    )
    (net (code "75") (name "VCC") (class "Default")
      (node (ref "C1") (pin "1") (pinfunction "1_1") (pintype "passive"))
      (node (ref "C16") (pin "2") (pinfunction "2_2") (pintype "passive"))
      (node (ref "C18") (pin "2") (pinfunction "2_2") (pintype "passive"))
      (node (ref "C19") (pin "2") (pinfunction "2_2") (pintype "passive"))
      (node (ref "C23") (pin "A") (pinfunction "+_A") (pintype "passive"))
      (node (ref "C3") (pin "1") (pinfunction "1_1") (pintype "passive"))
      (node (ref "D7") (pin "A") (pinfunction "A_A") (pintype "passive"))
      (node (ref "JP21") (pin "11") (pinfunction "11_11") (pintype "passive"))
      (node (ref "JP22") (pin "11") (pinfunction "11_11") (pintype "passive"))
      (node (ref "JP23") (pin "2") (pinfunction "2_2") (pintype "passive"))
      (node (ref "R10") (pin "1") (pinfunction "1_1") (pintype "passive"))
      (node (ref "R11") (pin "1") (pinfunction "CCW_1") (pintype "passive"))
      (node (ref "R21") (pin "2") (pinfunction "2_2") (pintype "passive"))
      (node (ref "R22") (pin "2") (pinfunction "2_2") (pintype "passive"))
      (node (ref "R23") (pin "2") (pinfunction "2_2") (pintype "passive"))
      (node (ref "R5") (pin "1") (pinfunction "1_1") (pintype "passive"))
      (node (ref "R6") (pin "1") (pinfunction "1_1") (pintype "passive"))
      (node (ref "R9") (pin "1") (pinfunction "1_1") (pintype "passive"))
      (node (ref "TP1") (pin "1") (pinfunction "1_1") (pintype "passive"))
      (node (ref "U1") (pin "P$15") (pinfunction "VDD_P$15") (pintype "power_in"))
      (node (ref "U2") (pin "P$15") (pinfunction "VDD_P$15") (pintype "power_in"))
      (node (ref "U3") (pin "28") (pinfunction "VDD_28") (pintype "power_in"))
      (node (ref "U3") (pin "37") (pinfunction "VUSB_37") (pintype "bidirectional"))
      (node (ref "U3") (pin "7") (pinfunction "VDD_7") (pintype "power_in"))
      (node (ref "U4") (pin "4") (pinfunction "OUT_4") (pintype "output"))
    )
    (net (code "76") (name "unconnected-(U1-NC-PadP$7)") (class "Default")
      (node (ref "U1") (pin "P$7") (pinfunction "NC_P$7") (pintype "no_connect"))
    )
    (net (code "77") (name "unconnected-(U1-NC-PadP$20)") (class "Default")
      (node (ref "U1") (pin "P$20") (pinfunction "NC_P$20") (pintype "no_connect"))
    )
    (net (code "78") (name "unconnected-(U1-NC-PadP$25)") (class "Default")
      (node (ref "U1") (pin "P$25") (pinfunction "NC_P$25") (pintype "no_connect"))
    )
    (net (code "79") (name "unconnected-(U2-NC-PadP$7)") (class "Default")
      (node (ref "U2") (pin "P$7") (pinfunction "NC_P$7") (pintype "no_connect"))
    )
    (net (code "80") (name "unconnected-(U2-NC-PadP$20)") (class "Default")
      (node (ref "U2") (pin "P$20") (pinfunction "NC_P$20") (pintype "no_connect"))
    )
    (net (code "81") (name "unconnected-(U2-NC-PadP$25)") (class "Default")
      (node (ref "U2") (pin "P$25") (pinfunction "NC_P$25") (pintype "no_connect"))
    )
    (net (code "82") (name "unconnected-(U3-NC-Pad12)") (class "Default")
      (node (ref "U3") (pin "12") (pinfunction "NC_12") (pintype "bidirectional"))
    )
    (net (code "83") (name "unconnected-(U3-NC-Pad13)") (class "Default")
      (node (ref "U3") (pin "13") (pinfunction "NC_13") (pintype "bidirectional"))
    )
    (net (code "84") (name "unconnected-(U3-NC-Pad33)") (class "Default")
      (node (ref "U3") (pin "33") (pinfunction "NC_33") (pintype "input"))
    )
    (net (code "85") (name "unconnected-(U3-NC-Pad34)") (class "Default")
      (node (ref "U3") (pin "34") (pinfunction "NC_34") (pintype "input"))
    )
  )
)
